# rp-schield.net
KiCad netlist of a schematic drawn in EAGLE
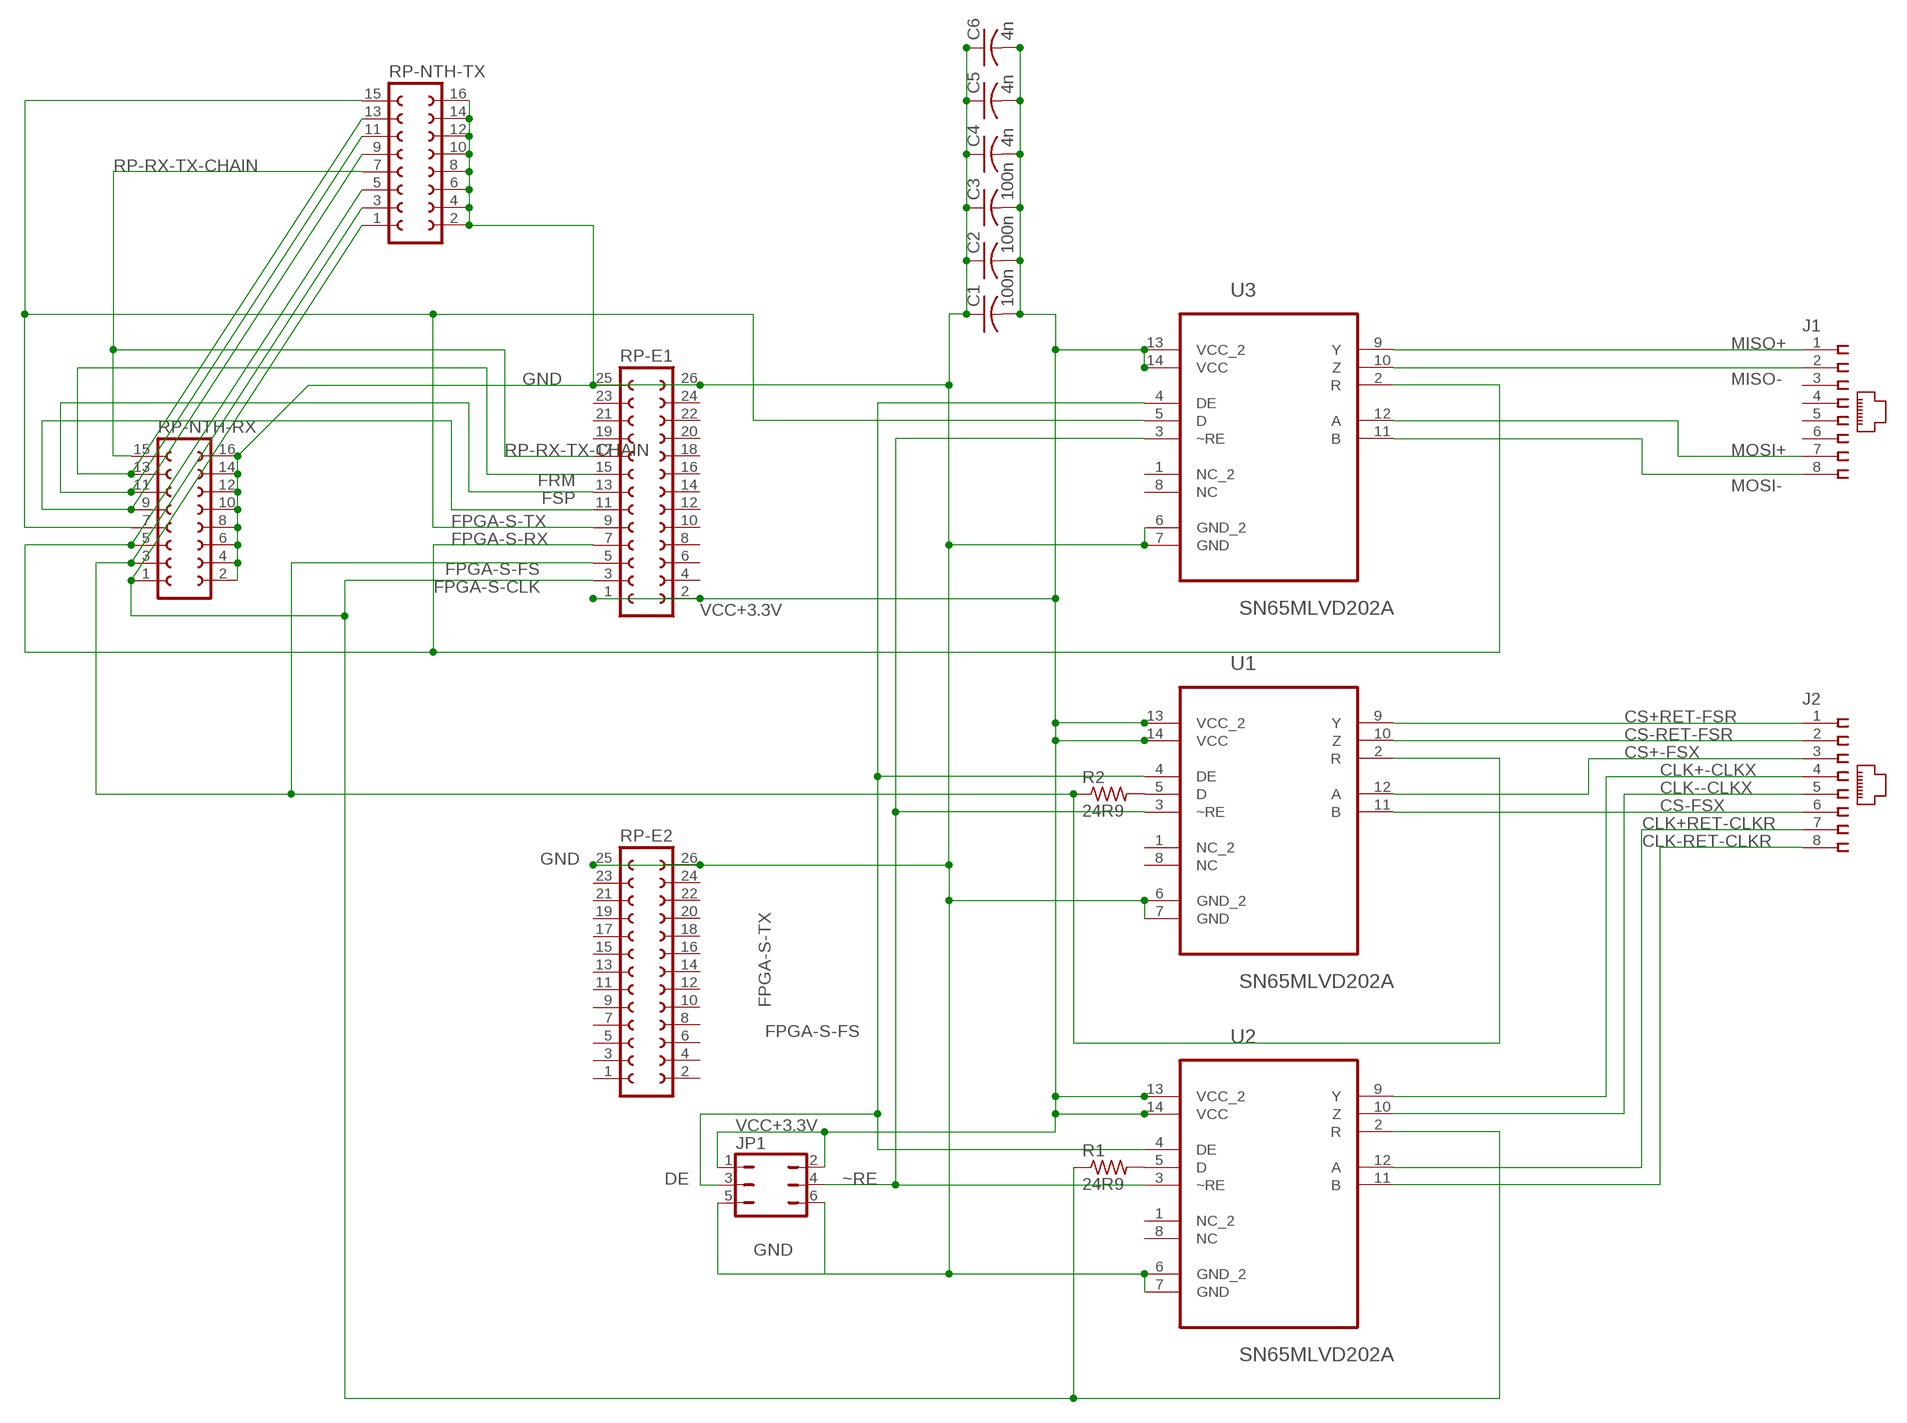
[diagram p0: schematic, sheet 1]

(export (version "E")
  (design (tool "Eeschema 10.0.6"))
  (components
    (comp (ref "C1")
      (value "100n")
      (footprint "eagle-import:C0805")
      (libsource (lib "eagle-import") (part "C-USC0805"))
    )
    (comp (ref "C2")
      (value "100n")
      (footprint "eagle-import:C0805")
      (libsource (lib "eagle-import") (part "C-USC0805"))
    )
    (comp (ref "C3")
      (value "100n")
      (footprint "eagle-import:C0805")
      (libsource (lib "eagle-import") (part "C-USC0805"))
    )
    (comp (ref "C4")
      (value "4n")
      (footprint "eagle-import:C0805")
      (libsource (lib "eagle-import") (part "C-USC0805"))
    )
    (comp (ref "C5")
      (value "4n")
      (footprint "eagle-import:C0805")
      (libsource (lib "eagle-import") (part "C-USC0805"))
    )
    (comp (ref "C6")
      (value "4n")
      (footprint "eagle-import:C0805")
      (libsource (lib "eagle-import") (part "C-USC0805"))
    )
    (comp (ref "J1")
      (value "557785-1-SHIELD")
      (footprint "eagle-import:557785-1")
      (libsource (lib "eagle-import") (part "557785-1-SHIELD"))
    )
    (comp (ref "J2")
      (value "557785-1-SHIELD")
      (footprint "eagle-import:557785-1")
      (libsource (lib "eagle-import") (part "557785-1-SHIELD"))
    )
    (comp (ref "JP1")
      (value "JP3Q")
      (footprint "eagle-import:JP3Q")
      (libsource (lib "eagle-import") (part "JP3Q"))
    )
    (comp (ref "R1")
      (value "24R9")
      (footprint "eagle-import:M1206")
      (libsource (lib "eagle-import") (part "R-US_M1206"))
    )
    (comp (ref "R2")
      (value "24R9")
      (footprint "eagle-import:M1206")
      (libsource (lib "eagle-import") (part "R-US_M1206"))
    )
    (comp (ref "RP-E1")
      (value "FE13-2")
      (footprint "eagle-import:FE13-2")
      (libsource (lib "eagle-import") (part "FE13-2"))
    )
    (comp (ref "RP-E2")
      (value "FE13-2")
      (footprint "eagle-import:FE13-2")
      (libsource (lib "eagle-import") (part "FE13-2"))
    )
    (comp (ref "RP-NTH-RX")
      (value "FE08-2")
      (footprint "eagle-import:FE08-2")
      (libsource (lib "eagle-import") (part "FE08-2"))
    )
    (comp (ref "RP-NTH-TX")
      (value "FE08-2")
      (footprint "eagle-import:FE08-2")
      (libsource (lib "eagle-import") (part "FE08-2"))
    )
    (comp (ref "U1")
      (value "SN65MLVD202A")
      (footprint "eagle-import:SOIC127P600X175-14N")
      (fields (field (name "MPN") "SN65MLVD205AD"))
      (libsource (lib "eagle-import") (part "SN65MLVD205AD"))
    )
    (comp (ref "U2")
      (value "SN65MLVD202A")
      (footprint "eagle-import:SOIC127P600X175-14N")
      (fields (field (name "MPN") "SN65MLVD205AD"))
      (libsource (lib "eagle-import") (part "SN65MLVD205AD"))
    )
    (comp (ref "U3")
      (value "SN65MLVD202A")
      (footprint "eagle-import:SOIC127P600X175-14N")
      (fields (field (name "MPN") "SN65MLVD205AD"))
      (libsource (lib "eagle-import") (part "SN65MLVD205AD"))
    )
  )
  (nets
    (net (code "1") (name "/CLK+-CLKX") (class "Default")
      (node (ref "J2") (pin "4") (pinfunction "4_4") (pintype "passive"))
      (node (ref "U2") (pin "9") (pinfunction "Y_9") (pintype "output"))
    )
    (net (code "2") (name "/CLK+RET-CLKR") (class "Default")
      (node (ref "J2") (pin "7") (pinfunction "7_7") (pintype "passive"))
      (node (ref "U2") (pin "12") (pinfunction "A_12") (pintype "output"))
    )
    (net (code "3") (name "/CLK--CLKX") (class "Default")
      (node (ref "J2") (pin "5") (pinfunction "5_5") (pintype "passive"))
      (node (ref "U2") (pin "10") (pinfunction "Z_10") (pintype "output"))
    )
    (net (code "4") (name "/CLK-RET-CLKR") (class "Default")
      (node (ref "J2") (pin "8") (pinfunction "8_8") (pintype "passive"))
      (node (ref "U2") (pin "11") (pinfunction "B_11") (pintype "output"))
    )
    (net (code "5") (name "/CS+-FSX") (class "Default")
      (node (ref "J2") (pin "3") (pinfunction "3_3") (pintype "passive"))
      (node (ref "U1") (pin "12") (pinfunction "A_12") (pintype "output"))
    )
    (net (code "6") (name "/CS+RET-FSR") (class "Default")
      (node (ref "J2") (pin "1") (pinfunction "1_1") (pintype "passive"))
      (node (ref "U1") (pin "9") (pinfunction "Y_9") (pintype "output"))
    )
    (net (code "7") (name "/CS-FSX") (class "Default")
      (node (ref "J2") (pin "6") (pinfunction "6_6") (pintype "passive"))
      (node (ref "U1") (pin "11") (pinfunction "B_11") (pintype "output"))
    )
    (net (code "8") (name "/CS-RET-FSR") (class "Default")
      (node (ref "J2") (pin "2") (pinfunction "2_2") (pintype "passive"))
      (node (ref "U1") (pin "10") (pinfunction "Z_10") (pintype "output"))
    )
    (net (code "9") (name "/DE") (class "Default")
      (node (ref "JP1") (pin "3") (pinfunction "3_3") (pintype "passive"))
      (node (ref "U1") (pin "4") (pinfunction "DE_4") (pintype "input"))
      (node (ref "U2") (pin "4") (pinfunction "DE_4") (pintype "input"))
      (node (ref "U3") (pin "4") (pinfunction "DE_4") (pintype "input"))
    )
    (net (code "10") (name "/FPGA-S-CLK") (class "Default")
      (node (ref "R1") (pin "1") (pinfunction "1_1") (pintype "passive"))
      (node (ref "RP-E1") (pin "3") (pinfunction "3_3") (pintype "passive"))
      (node (ref "RP-NTH-RX") (pin "1") (pinfunction "1_1") (pintype "passive"))
      (node (ref "RP-NTH-TX") (pin "1") (pinfunction "1_1") (pintype "passive"))
      (node (ref "U2") (pin "2") (pinfunction "R_2") (pintype "output"))
    )
    (net (code "11") (name "/FPGA-S-FS") (class "Default")
      (node (ref "R2") (pin "1") (pinfunction "1_1") (pintype "passive"))
      (node (ref "RP-E1") (pin "5") (pinfunction "5_5") (pintype "passive"))
      (node (ref "RP-NTH-RX") (pin "3") (pinfunction "3_3") (pintype "passive"))
      (node (ref "RP-NTH-TX") (pin "3") (pinfunction "3_3") (pintype "passive"))
      (node (ref "U1") (pin "2") (pinfunction "R_2") (pintype "output"))
    )
    (net (code "12") (name "/FPGA-S-RX") (class "Default")
      (node (ref "RP-E1") (pin "7") (pinfunction "7_7") (pintype "passive"))
      (node (ref "RP-NTH-RX") (pin "5") (pinfunction "5_5") (pintype "passive"))
      (node (ref "RP-NTH-TX") (pin "5") (pinfunction "5_5") (pintype "passive"))
      (node (ref "U3") (pin "2") (pinfunction "R_2") (pintype "output"))
    )
    (net (code "13") (name "/FPGA-S-TX") (class "Default")
      (node (ref "RP-E1") (pin "9") (pinfunction "9_9") (pintype "passive"))
      (node (ref "RP-NTH-RX") (pin "7") (pinfunction "7_7") (pintype "passive"))
      (node (ref "RP-NTH-TX") (pin "15") (pinfunction "15_15") (pintype "passive"))
      (node (ref "U3") (pin "5") (pinfunction "D_5") (pintype "input"))
    )
    (net (code "14") (name "/FRM") (class "Default")
      (node (ref "RP-E1") (pin "13") (pinfunction "13_13") (pintype "passive"))
      (node (ref "RP-NTH-RX") (pin "11") (pinfunction "11_11") (pintype "passive"))
      (node (ref "RP-NTH-TX") (pin "11") (pinfunction "11_11") (pintype "passive"))
    )
    (net (code "15") (name "/FSP") (class "Default")
      (node (ref "RP-E1") (pin "11") (pinfunction "11_11") (pintype "passive"))
      (node (ref "RP-NTH-RX") (pin "9") (pinfunction "9_9") (pintype "passive"))
      (node (ref "RP-NTH-TX") (pin "9") (pinfunction "9_9") (pintype "passive"))
    )
    (net (code "16") (name "/GND") (class "Default")
      (node (ref "C1") (pin "1") (pinfunction "1_1") (pintype "passive"))
      (node (ref "C2") (pin "1") (pinfunction "1_1") (pintype "passive"))
      (node (ref "C3") (pin "1") (pinfunction "1_1") (pintype "passive"))
      (node (ref "C4") (pin "1") (pinfunction "1_1") (pintype "passive"))
      (node (ref "C5") (pin "1") (pinfunction "1_1") (pintype "passive"))
      (node (ref "C6") (pin "1") (pinfunction "1_1") (pintype "passive"))
      (node (ref "JP1") (pin "5") (pinfunction "5_5") (pintype "passive"))
      (node (ref "JP1") (pin "6") (pinfunction "6_6") (pintype "passive"))
      (node (ref "RP-E1") (pin "25") (pinfunction "25_25") (pintype "passive"))
      (node (ref "RP-E1") (pin "26") (pinfunction "26_26") (pintype "passive"))
      (node (ref "RP-E2") (pin "25") (pinfunction "25_25") (pintype "passive"))
      (node (ref "RP-E2") (pin "26") (pinfunction "26_26") (pintype "passive"))
      (node (ref "RP-NTH-RX") (pin "10") (pinfunction "10_10") (pintype "passive"))
      (node (ref "RP-NTH-RX") (pin "12") (pinfunction "12_12") (pintype "passive"))
      (node (ref "RP-NTH-RX") (pin "14") (pinfunction "14_14") (pintype "passive"))
      (node (ref "RP-NTH-RX") (pin "16") (pinfunction "16_16") (pintype "passive"))
      (node (ref "RP-NTH-RX") (pin "2") (pinfunction "2_2") (pintype "passive"))
      (node (ref "RP-NTH-RX") (pin "4") (pinfunction "4_4") (pintype "passive"))
      (node (ref "RP-NTH-RX") (pin "6") (pinfunction "6_6") (pintype "passive"))
      (node (ref "RP-NTH-RX") (pin "8") (pinfunction "8_8") (pintype "passive"))
      (node (ref "RP-NTH-TX") (pin "10") (pinfunction "10_10") (pintype "passive"))
      (node (ref "RP-NTH-TX") (pin "12") (pinfunction "12_12") (pintype "passive"))
      (node (ref "RP-NTH-TX") (pin "14") (pinfunction "14_14") (pintype "passive"))
      (node (ref "RP-NTH-TX") (pin "16") (pinfunction "16_16") (pintype "passive"))
      (node (ref "RP-NTH-TX") (pin "2") (pinfunction "2_2") (pintype "passive"))
      (node (ref "RP-NTH-TX") (pin "4") (pinfunction "4_4") (pintype "passive"))
      (node (ref "RP-NTH-TX") (pin "6") (pinfunction "6_6") (pintype "passive"))
      (node (ref "RP-NTH-TX") (pin "8") (pinfunction "8_8") (pintype "passive"))
      (node (ref "U1") (pin "6") (pinfunction "GND_2_6") (pintype "passive"))
      (node (ref "U1") (pin "7") (pinfunction "GND_7") (pintype "passive"))
      (node (ref "U2") (pin "6") (pinfunction "GND_2_6") (pintype "passive"))
      (node (ref "U2") (pin "7") (pinfunction "GND_7") (pintype "passive"))
      (node (ref "U3") (pin "6") (pinfunction "GND_2_6") (pintype "passive"))
      (node (ref "U3") (pin "7") (pinfunction "GND_7") (pintype "passive"))
    )
    (net (code "17") (name "/MISO+") (class "Default")
      (node (ref "J1") (pin "1") (pinfunction "1_1") (pintype "passive"))
      (node (ref "U3") (pin "9") (pinfunction "Y_9") (pintype "output"))
    )
    (net (code "18") (name "/MISO-") (class "Default")
      (node (ref "J1") (pin "2") (pinfunction "2_2") (pintype "passive"))
      (node (ref "U3") (pin "10") (pinfunction "Z_10") (pintype "output"))
    )
    (net (code "19") (name "/MOSI+") (class "Default")
      (node (ref "J1") (pin "7") (pinfunction "7_7") (pintype "passive"))
      (node (ref "U3") (pin "12") (pinfunction "A_12") (pintype "output"))
    )
    (net (code "20") (name "/MOSI-") (class "Default")
      (node (ref "J1") (pin "8") (pinfunction "8_8") (pintype "passive"))
      (node (ref "U3") (pin "11") (pinfunction "B_11") (pintype "output"))
    )
    (net (code "21") (name "/RP-RX-TX-CHAIN") (class "Default")
      (node (ref "RP-E1") (pin "17") (pinfunction "17_17") (pintype "passive"))
      (node (ref "RP-NTH-RX") (pin "15") (pinfunction "15_15") (pintype "passive"))
      (node (ref "RP-NTH-TX") (pin "7") (pinfunction "7_7") (pintype "passive"))
    )
    (net (code "22") (name "/VCC+3.3V") (class "Default")
      (node (ref "C1") (pin "2") (pinfunction "2_2") (pintype "passive"))
      (node (ref "C2") (pin "2") (pinfunction "2_2") (pintype "passive"))
      (node (ref "C3") (pin "2") (pinfunction "2_2") (pintype "passive"))
      (node (ref "C4") (pin "2") (pinfunction "2_2") (pintype "passive"))
      (node (ref "C5") (pin "2") (pinfunction "2_2") (pintype "passive"))
      (node (ref "C6") (pin "2") (pinfunction "2_2") (pintype "passive"))
      (node (ref "JP1") (pin "1") (pinfunction "1_1") (pintype "passive"))
      (node (ref "JP1") (pin "2") (pinfunction "2_2") (pintype "passive"))
      (node (ref "RP-E1") (pin "1") (pinfunction "1_1") (pintype "passive"))
      (node (ref "RP-E1") (pin "2") (pinfunction "2_2") (pintype "passive"))
      (node (ref "U1") (pin "13") (pinfunction "VCC_2_13") (pintype "power_in"))
      (node (ref "U1") (pin "14") (pinfunction "VCC_14") (pintype "power_in"))
      (node (ref "U2") (pin "13") (pinfunction "VCC_2_13") (pintype "power_in"))
      (node (ref "U2") (pin "14") (pinfunction "VCC_14") (pintype "power_in"))
      (node (ref "U3") (pin "13") (pinfunction "VCC_2_13") (pintype "power_in"))
      (node (ref "U3") (pin "14") (pinfunction "VCC_14") (pintype "power_in"))
    )
    (net (code "23") (name "/~{RE}") (class "Default")
      (node (ref "JP1") (pin "4") (pinfunction "4_4") (pintype "passive"))
      (node (ref "U1") (pin "3") (pinfunction "~{RE}_3") (pintype "input"))
      (node (ref "U2") (pin "3") (pinfunction "~{RE}_3") (pintype "input"))
      (node (ref "U3") (pin "3") (pinfunction "~{RE}_3") (pintype "input"))
    )
    (net (code "24") (name "Net-(RP-E1-Pad15)") (class "Default")
      (node (ref "RP-E1") (pin "15") (pinfunction "15_15") (pintype "passive"))
      (node (ref "RP-NTH-RX") (pin "13") (pinfunction "13_13") (pintype "passive"))
      (node (ref "RP-NTH-TX") (pin "13") (pinfunction "13_13") (pintype "passive"))
    )
    (net (code "25") (name "Net-(U1-D)") (class "Default")
      (node (ref "R2") (pin "2") (pinfunction "2_2") (pintype "passive"))
      (node (ref "U1") (pin "5") (pinfunction "D_5") (pintype "input"))
    )
    (net (code "26") (name "Net-(U2-D)") (class "Default")
      (node (ref "R1") (pin "2") (pinfunction "2_2") (pintype "passive"))
      (node (ref "U2") (pin "5") (pinfunction "D_5") (pintype "input"))
    )
    (net (code "27") (name "unconnected-(J1-Pad3)") (class "Default")
      (node (ref "J1") (pin "3") (pinfunction "3_3") (pintype "passive"))
    )
    (net (code "28") (name "unconnected-(J1-Pad4)") (class "Default")
      (node (ref "J1") (pin "4") (pinfunction "4_4") (pintype "passive"))
    )
    (net (code "29") (name "unconnected-(J1-Pad5)") (class "Default")
      (node (ref "J1") (pin "5") (pinfunction "5_5") (pintype "passive"))
    )
    (net (code "30") (name "unconnected-(J1-Pad6)") (class "Default")
      (node (ref "J1") (pin "6") (pinfunction "6_6") (pintype "passive"))
    )
    (net (code "31") (name "unconnected-(RP-E1-Pad4)") (class "Default")
      (node (ref "RP-E1") (pin "4") (pinfunction "4_4") (pintype "passive"))
    )
    (net (code "32") (name "unconnected-(RP-E1-Pad6)") (class "Default")
      (node (ref "RP-E1") (pin "6") (pinfunction "6_6") (pintype "passive"))
    )
    (net (code "33") (name "unconnected-(RP-E1-Pad8)") (class "Default")
      (node (ref "RP-E1") (pin "8") (pinfunction "8_8") (pintype "passive"))
    )
    (net (code "34") (name "unconnected-(RP-E1-Pad10)") (class "Default")
      (node (ref "RP-E1") (pin "10") (pinfunction "10_10") (pintype "passive"))
    )
    (net (code "35") (name "unconnected-(RP-E1-Pad12)") (class "Default")
      (node (ref "RP-E1") (pin "12") (pinfunction "12_12") (pintype "passive"))
    )
    (net (code "36") (name "unconnected-(RP-E1-Pad14)") (class "Default")
      (node (ref "RP-E1") (pin "14") (pinfunction "14_14") (pintype "passive"))
    )
    (net (code "37") (name "unconnected-(RP-E1-Pad16)") (class "Default")
      (node (ref "RP-E1") (pin "16") (pinfunction "16_16") (pintype "passive"))
    )
    (net (code "38") (name "unconnected-(RP-E1-Pad18)") (class "Default")
      (node (ref "RP-E1") (pin "18") (pinfunction "18_18") (pintype "passive"))
    )
    (net (code "39") (name "unconnected-(RP-E1-Pad19)") (class "Default")
      (node (ref "RP-E1") (pin "19") (pinfunction "19_19") (pintype "passive"))
    )
    (net (code "40") (name "unconnected-(RP-E1-Pad20)") (class "Default")
      (node (ref "RP-E1") (pin "20") (pinfunction "20_20") (pintype "passive"))
    )
    (net (code "41") (name "unconnected-(RP-E1-Pad21)") (class "Default")
      (node (ref "RP-E1") (pin "21") (pinfunction "21_21") (pintype "passive"))
    )
    (net (code "42") (name "unconnected-(RP-E1-Pad22)") (class "Default")
      (node (ref "RP-E1") (pin "22") (pinfunction "22_22") (pintype "passive"))
    )
    (net (code "43") (name "unconnected-(RP-E1-Pad23)") (class "Default")
      (node (ref "RP-E1") (pin "23") (pinfunction "23_23") (pintype "passive"))
    )
    (net (code "44") (name "unconnected-(RP-E1-Pad24)") (class "Default")
      (node (ref "RP-E1") (pin "24") (pinfunction "24_24") (pintype "passive"))
    )
    (net (code "45") (name "unconnected-(RP-E2-Pad1)") (class "Default")
      (node (ref "RP-E2") (pin "1") (pinfunction "1_1") (pintype "passive"))
    )
    (net (code "46") (name "unconnected-(RP-E2-Pad2)") (class "Default")
      (node (ref "RP-E2") (pin "2") (pinfunction "2_2") (pintype "passive"))
    )
    (net (code "47") (name "unconnected-(RP-E2-Pad3)") (class "Default")
      (node (ref "RP-E2") (pin "3") (pinfunction "3_3") (pintype "passive"))
    )
    (net (code "48") (name "unconnected-(RP-E2-Pad4)") (class "Default")
      (node (ref "RP-E2") (pin "4") (pinfunction "4_4") (pintype "passive"))
    )
    (net (code "49") (name "unconnected-(RP-E2-Pad5)") (class "Default")
      (node (ref "RP-E2") (pin "5") (pinfunction "5_5") (pintype "passive"))
    )
    (net (code "50") (name "unconnected-(RP-E2-Pad6)") (class "Default")
      (node (ref "RP-E2") (pin "6") (pinfunction "6_6") (pintype "passive"))
    )
    (net (code "51") (name "unconnected-(RP-E2-Pad7)") (class "Default")
      (node (ref "RP-E2") (pin "7") (pinfunction "7_7") (pintype "passive"))
    )
    (net (code "52") (name "unconnected-(RP-E2-Pad8)") (class "Default")
      (node (ref "RP-E2") (pin "8") (pinfunction "8_8") (pintype "passive"))
    )
    (net (code "53") (name "unconnected-(RP-E2-Pad9)") (class "Default")
      (node (ref "RP-E2") (pin "9") (pinfunction "9_9") (pintype "passive"))
    )
    (net (code "54") (name "unconnected-(RP-E2-Pad10)") (class "Default")
      (node (ref "RP-E2") (pin "10") (pinfunction "10_10") (pintype "passive"))
    )
    (net (code "55") (name "unconnected-(RP-E2-Pad11)") (class "Default")
      (node (ref "RP-E2") (pin "11") (pinfunction "11_11") (pintype "passive"))
    )
    (net (code "56") (name "unconnected-(RP-E2-Pad12)") (class "Default")
      (node (ref "RP-E2") (pin "12") (pinfunction "12_12") (pintype "passive"))
    )
    (net (code "57") (name "unconnected-(RP-E2-Pad13)") (class "Default")
      (node (ref "RP-E2") (pin "13") (pinfunction "13_13") (pintype "passive"))
    )
    (net (code "58") (name "unconnected-(RP-E2-Pad14)") (class "Default")
      (node (ref "RP-E2") (pin "14") (pinfunction "14_14") (pintype "passive"))
    )
    (net (code "59") (name "unconnected-(RP-E2-Pad15)") (class "Default")
      (node (ref "RP-E2") (pin "15") (pinfunction "15_15") (pintype "passive"))
    )
    (net (code "60") (name "unconnected-(RP-E2-Pad16)") (class "Default")
      (node (ref "RP-E2") (pin "16") (pinfunction "16_16") (pintype "passive"))
    )
    (net (code "61") (name "unconnected-(RP-E2-Pad17)") (class "Default")
      (node (ref "RP-E2") (pin "17") (pinfunction "17_17") (pintype "passive"))
    )
    (net (code "62") (name "unconnected-(RP-E2-Pad18)") (class "Default")
      (node (ref "RP-E2") (pin "18") (pinfunction "18_18") (pintype "passive"))
    )
    (net (code "63") (name "unconnected-(RP-E2-Pad19)") (class "Default")
      (node (ref "RP-E2") (pin "19") (pinfunction "19_19") (pintype "passive"))
    )
    (net (code "64") (name "unconnected-(RP-E2-Pad20)") (class "Default")
      (node (ref "RP-E2") (pin "20") (pinfunction "20_20") (pintype "passive"))
    )
    (net (code "65") (name "unconnected-(RP-E2-Pad21)") (class "Default")
      (node (ref "RP-E2") (pin "21") (pinfunction "21_21") (pintype "passive"))
    )
    (net (code "66") (name "unconnected-(RP-E2-Pad22)") (class "Default")
      (node (ref "RP-E2") (pin "22") (pinfunction "22_22") (pintype "passive"))
    )
    (net (code "67") (name "unconnected-(RP-E2-Pad23)") (class "Default")
      (node (ref "RP-E2") (pin "23") (pinfunction "23_23") (pintype "passive"))
    )
    (net (code "68") (name "unconnected-(RP-E2-Pad24)") (class "Default")
      (node (ref "RP-E2") (pin "24") (pinfunction "24_24") (pintype "passive"))
    )
    (net (code "69") (name "unconnected-(U1-NC-Pad8)") (class "Default")
      (node (ref "U1") (pin "8") (pinfunction "NC_8") (pintype "no_connect"))
    )
    (net (code "70") (name "unconnected-(U1-NC_2-Pad1)") (class "Default")
      (node (ref "U1") (pin "1") (pinfunction "NC_2_1") (pintype "no_connect"))
    )
    (net (code "71") (name "unconnected-(U2-NC-Pad8)") (class "Default")
      (node (ref "U2") (pin "8") (pinfunction "NC_8") (pintype "no_connect"))
    )
    (net (code "72") (name "unconnected-(U2-NC_2-Pad1)") (class "Default")
      (node (ref "U2") (pin "1") (pinfunction "NC_2_1") (pintype "no_connect"))
    )
    (net (code "73") (name "unconnected-(U3-NC-Pad8)") (class "Default")
      (node (ref "U3") (pin "8") (pinfunction "NC_8") (pintype "no_connect"))
    )
    (net (code "74") (name "unconnected-(U3-NC_2-Pad1)") (class "Default")
      (node (ref "U3") (pin "1") (pinfunction "NC_2_1") (pintype "no_connect"))
    )
  )
)
